# detectino.net
KiCad netlist of a schematic drawn in EAGLE
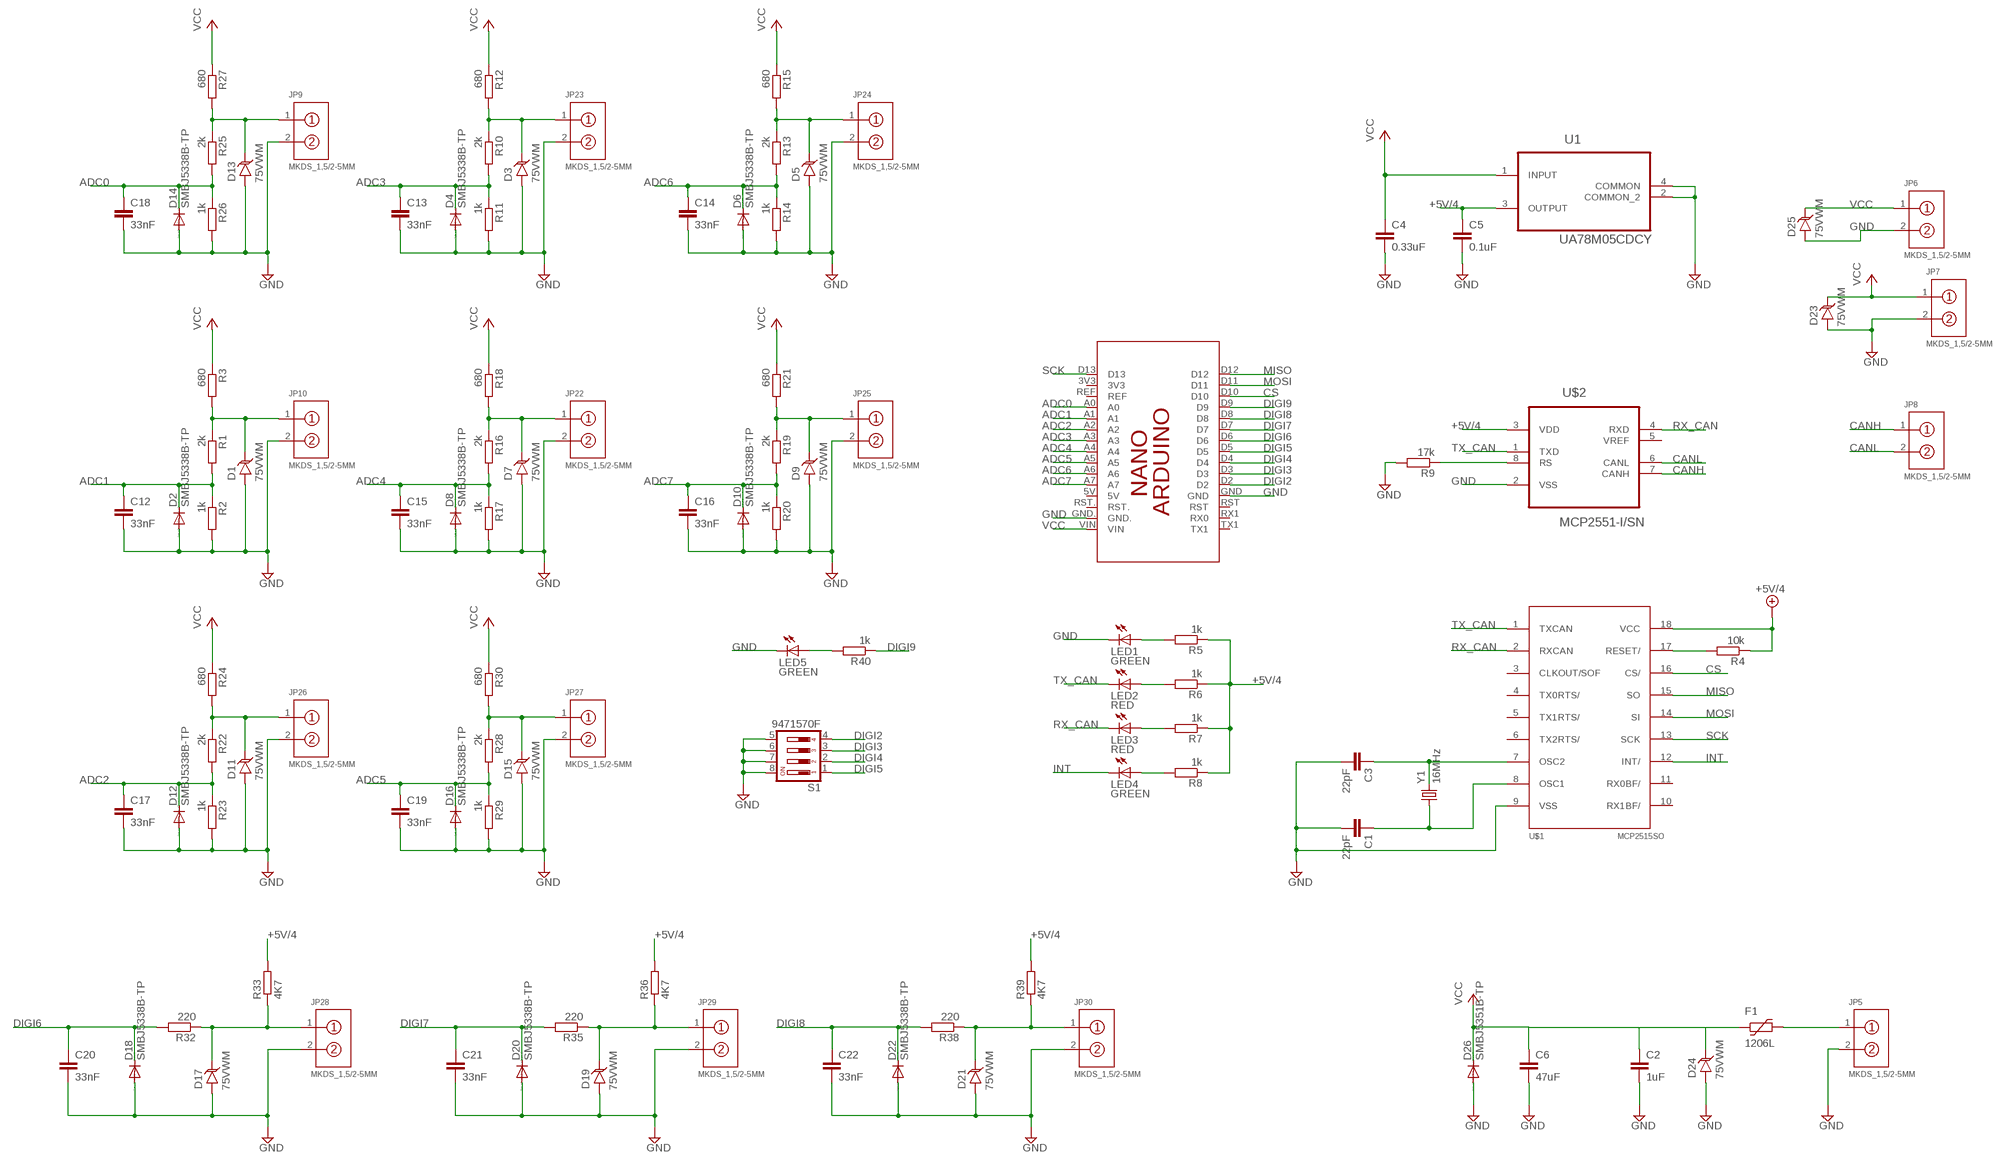
[diagram p0: schematic, sheet 1]

(export (version "E")
  (design (tool "Eeschema 10.0.6"))
  (components
    (comp (ref "C1")
      (value "22pF")
      (footprint "eagle-import:C1206K")
      (libsource (lib "eagle-import") (part "C-EUC1206K"))
    )
    (comp (ref "C2")
      (value "1uF")
      (footprint "eagle-import:C1206K")
      (libsource (lib "eagle-import") (part "C-EUC1206K"))
    )
    (comp (ref "C3")
      (value "22pF")
      (footprint "eagle-import:C1206K")
      (libsource (lib "eagle-import") (part "C-EUC1206K"))
    )
    (comp (ref "C4")
      (value "0.33uF")
      (footprint "eagle-import:C1206K")
      (libsource (lib "eagle-import") (part "C-EUC1206K"))
    )
    (comp (ref "C5")
      (value "0.1uF")
      (footprint "eagle-import:C1206K")
      (libsource (lib "eagle-import") (part "C-EUC1206K"))
    )
    (comp (ref "C6")
      (value "47uF")
      (footprint "eagle-import:C1206K")
      (libsource (lib "eagle-import") (part "C-EUC1206K"))
    )
    (comp (ref "C12")
      (value "33nF")
      (footprint "eagle-import:C1206K")
      (libsource (lib "eagle-import") (part "C-EUC1206K"))
    )
    (comp (ref "C13")
      (value "33nF")
      (footprint "eagle-import:C1206K")
      (libsource (lib "eagle-import") (part "C-EUC1206K"))
    )
    (comp (ref "C14")
      (value "33nF")
      (footprint "eagle-import:C1206K")
      (libsource (lib "eagle-import") (part "C-EUC1206K"))
    )
    (comp (ref "C15")
      (value "33nF")
      (footprint "eagle-import:C1206K")
      (libsource (lib "eagle-import") (part "C-EUC1206K"))
    )
    (comp (ref "C16")
      (value "33nF")
      (footprint "eagle-import:C1206K")
      (libsource (lib "eagle-import") (part "C-EUC1206K"))
    )
    (comp (ref "C17")
      (value "33nF")
      (footprint "eagle-import:C1206K")
      (libsource (lib "eagle-import") (part "C-EUC1206K"))
    )
    (comp (ref "C18")
      (value "33nF")
      (footprint "eagle-import:C1206K")
      (libsource (lib "eagle-import") (part "C-EUC1206K"))
    )
    (comp (ref "C19")
      (value "33nF")
      (footprint "eagle-import:C1206K")
      (libsource (lib "eagle-import") (part "C-EUC1206K"))
    )
    (comp (ref "C20")
      (value "33nF")
      (footprint "eagle-import:C1206K")
      (libsource (lib "eagle-import") (part "C-EUC1206K"))
    )
    (comp (ref "C21")
      (value "33nF")
      (footprint "eagle-import:C1206K")
      (libsource (lib "eagle-import") (part "C-EUC1206K"))
    )
    (comp (ref "C22")
      (value "33nF")
      (footprint "eagle-import:C1206K")
      (libsource (lib "eagle-import") (part "C-EUC1206K"))
    )
    (comp (ref "D1")
      (value "75VWM")
      (footprint "eagle-import:SMC")
      (libsource (lib "eagle-import") (part "TVS75VWM"))
    )
    (comp (ref "D2")
      (value "SMBJ5338B-TP")
      (footprint "eagle-import:DO214AA")
      (libsource (lib "eagle-import") (part "DIODE-DO214AA"))
    )
    (comp (ref "D3")
      (value "75VWM")
      (footprint "eagle-import:SMC")
      (libsource (lib "eagle-import") (part "TVS75VWM"))
    )
    (comp (ref "D4")
      (value "SMBJ5338B-TP")
      (footprint "eagle-import:DO214AA")
      (libsource (lib "eagle-import") (part "DIODE-DO214AA"))
    )
    (comp (ref "D5")
      (value "75VWM")
      (footprint "eagle-import:SMC")
      (libsource (lib "eagle-import") (part "TVS75VWM"))
    )
    (comp (ref "D6")
      (value "SMBJ5338B-TP")
      (footprint "eagle-import:DO214AA")
      (libsource (lib "eagle-import") (part "DIODE-DO214AA"))
    )
    (comp (ref "D7")
      (value "75VWM")
      (footprint "eagle-import:SMC")
      (libsource (lib "eagle-import") (part "TVS75VWM"))
    )
    (comp (ref "D8")
      (value "SMBJ5338B-TP")
      (footprint "eagle-import:DO214AA")
      (libsource (lib "eagle-import") (part "DIODE-DO214AA"))
    )
    (comp (ref "D9")
      (value "75VWM")
      (footprint "eagle-import:SMC")
      (libsource (lib "eagle-import") (part "TVS75VWM"))
    )
    (comp (ref "D10")
      (value "SMBJ5338B-TP")
      (footprint "eagle-import:DO214AA")
      (libsource (lib "eagle-import") (part "DIODE-DO214AA"))
    )
    (comp (ref "D11")
      (value "75VWM")
      (footprint "eagle-import:SMC")
      (libsource (lib "eagle-import") (part "TVS75VWM"))
    )
    (comp (ref "D12")
      (value "SMBJ5338B-TP")
      (footprint "eagle-import:DO214AA")
      (libsource (lib "eagle-import") (part "DIODE-DO214AA"))
    )
    (comp (ref "D13")
      (value "75VWM")
      (footprint "eagle-import:SMC")
      (libsource (lib "eagle-import") (part "TVS75VWM"))
    )
    (comp (ref "D14")
      (value "SMBJ5338B-TP")
      (footprint "eagle-import:DO214AA")
      (libsource (lib "eagle-import") (part "DIODE-DO214AA"))
    )
    (comp (ref "D15")
      (value "75VWM")
      (footprint "eagle-import:SMC")
      (libsource (lib "eagle-import") (part "TVS75VWM"))
    )
    (comp (ref "D16")
      (value "SMBJ5338B-TP")
      (footprint "eagle-import:DO214AA")
      (libsource (lib "eagle-import") (part "DIODE-DO214AA"))
    )
    (comp (ref "D17")
      (value "75VWM")
      (footprint "eagle-import:SMC")
      (libsource (lib "eagle-import") (part "TVS75VWM"))
    )
    (comp (ref "D18")
      (value "SMBJ5338B-TP")
      (footprint "eagle-import:DO214AA")
      (libsource (lib "eagle-import") (part "DIODE-DO214AA"))
    )
    (comp (ref "D19")
      (value "75VWM")
      (footprint "eagle-import:SMC")
      (libsource (lib "eagle-import") (part "TVS75VWM"))
    )
    (comp (ref "D20")
      (value "SMBJ5338B-TP")
      (footprint "eagle-import:DO214AA")
      (libsource (lib "eagle-import") (part "DIODE-DO214AA"))
    )
    (comp (ref "D21")
      (value "75VWM")
      (footprint "eagle-import:SMC")
      (libsource (lib "eagle-import") (part "TVS75VWM"))
    )
    (comp (ref "D22")
      (value "SMBJ5338B-TP")
      (footprint "eagle-import:DO214AA")
      (libsource (lib "eagle-import") (part "DIODE-DO214AA"))
    )
    (comp (ref "D23")
      (value "75VWM")
      (footprint "eagle-import:SMC")
      (libsource (lib "eagle-import") (part "TVS75VWM"))
    )
    (comp (ref "D24")
      (value "75VWM")
      (footprint "eagle-import:SMC")
      (libsource (lib "eagle-import") (part "TVS75VWM"))
    )
    (comp (ref "D25")
      (value "75VWM")
      (footprint "eagle-import:SMC")
      (libsource (lib "eagle-import") (part "TVS75VWM"))
    )
    (comp (ref "D26")
      (value "SMBJ5351B-TP")
      (footprint "eagle-import:DO214AA")
      (libsource (lib "eagle-import") (part "DIODE-DO214AA"))
    )
    (comp (ref "F1")
      (value "1206L")
      (footprint "eagle-import:1206L")
      (libsource (lib "eagle-import") (part "1206L"))
    )
    (comp (ref "JP5")
      (value "MKDS_1,5/2-5MM")
      (footprint "eagle-import:MKDS_1,5_2-5MM")
      (libsource (lib "eagle-import") (part "MKDS_1,5/2-5MM"))
    )
    (comp (ref "JP6")
      (value "MKDS_1,5/2-5MM")
      (footprint "eagle-import:MKDS_1,5_2-5MM")
      (libsource (lib "eagle-import") (part "MKDS_1,5/2-5MM"))
    )
    (comp (ref "JP7")
      (value "MKDS_1,5/2-5MM")
      (footprint "eagle-import:MKDS_1,5_2-5MM")
      (libsource (lib "eagle-import") (part "MKDS_1,5/2-5MM"))
    )
    (comp (ref "JP8")
      (value "MKDS_1,5/2-5MM")
      (footprint "eagle-import:MKDS_1,5_2-5MM")
      (libsource (lib "eagle-import") (part "MKDS_1,5/2-5MM"))
    )
    (comp (ref "JP9")
      (value "MKDS_1,5/2-5MM")
      (footprint "eagle-import:MKDS_1,5_2-5MM")
      (libsource (lib "eagle-import") (part "MKDS_1,5/2-5MM"))
    )
    (comp (ref "JP10")
      (value "MKDS_1,5/2-5MM")
      (footprint "eagle-import:MKDS_1,5_2-5MM")
      (libsource (lib "eagle-import") (part "MKDS_1,5/2-5MM"))
    )
    (comp (ref "JP22")
      (value "MKDS_1,5/2-5MM")
      (footprint "eagle-import:MKDS_1,5_2-5MM")
      (libsource (lib "eagle-import") (part "MKDS_1,5/2-5MM"))
    )
    (comp (ref "JP23")
      (value "MKDS_1,5/2-5MM")
      (footprint "eagle-import:MKDS_1,5_2-5MM")
      (libsource (lib "eagle-import") (part "MKDS_1,5/2-5MM"))
    )
    (comp (ref "JP24")
      (value "MKDS_1,5/2-5MM")
      (footprint "eagle-import:MKDS_1,5_2-5MM")
      (libsource (lib "eagle-import") (part "MKDS_1,5/2-5MM"))
    )
    (comp (ref "JP25")
      (value "MKDS_1,5/2-5MM")
      (footprint "eagle-import:MKDS_1,5_2-5MM")
      (libsource (lib "eagle-import") (part "MKDS_1,5/2-5MM"))
    )
    (comp (ref "JP26")
      (value "MKDS_1,5/2-5MM")
      (footprint "eagle-import:MKDS_1,5_2-5MM")
      (libsource (lib "eagle-import") (part "MKDS_1,5/2-5MM"))
    )
    (comp (ref "JP27")
      (value "MKDS_1,5/2-5MM")
      (footprint "eagle-import:MKDS_1,5_2-5MM")
      (libsource (lib "eagle-import") (part "MKDS_1,5/2-5MM"))
    )
    (comp (ref "JP28")
      (value "MKDS_1,5/2-5MM")
      (footprint "eagle-import:MKDS_1,5_2-5MM")
      (libsource (lib "eagle-import") (part "MKDS_1,5/2-5MM"))
    )
    (comp (ref "JP29")
      (value "MKDS_1,5/2-5MM")
      (footprint "eagle-import:MKDS_1,5_2-5MM")
      (libsource (lib "eagle-import") (part "MKDS_1,5/2-5MM"))
    )
    (comp (ref "JP30")
      (value "MKDS_1,5/2-5MM")
      (footprint "eagle-import:MKDS_1,5_2-5MM")
      (libsource (lib "eagle-import") (part "MKDS_1,5/2-5MM"))
    )
    (comp (ref "LED1")
      (value "GREEN")
      (footprint "eagle-import:SML1206")
      (libsource (lib "eagle-import") (part "LEDSML1206"))
    )
    (comp (ref "LED2")
      (value "RED")
      (footprint "eagle-import:SML1206")
      (libsource (lib "eagle-import") (part "LEDSML1206"))
    )
    (comp (ref "LED3")
      (value "RED")
      (footprint "eagle-import:SML1206")
      (libsource (lib "eagle-import") (part "LEDSML1206"))
    )
    (comp (ref "LED4")
      (value "GREEN")
      (footprint "eagle-import:SML1206")
      (libsource (lib "eagle-import") (part "LEDSML1206"))
    )
    (comp (ref "LED5")
      (value "GREEN")
      (footprint "eagle-import:SML1206")
      (libsource (lib "eagle-import") (part "LEDSML1206"))
    )
    (comp (ref "PCB2")
      (value "ARDUINO_NANO")
      (footprint "eagle-import:ARDUINO_NANO")
      (libsource (lib "eagle-import") (part "ARDUINO_NANO"))
    )
    (comp (ref "R1")
      (value "2k")
      (footprint "eagle-import:R1206")
      (libsource (lib "eagle-import") (part "R-EU_R1206"))
    )
    (comp (ref "R2")
      (value "1k")
      (footprint "eagle-import:R1206")
      (libsource (lib "eagle-import") (part "R-EU_R1206"))
    )
    (comp (ref "R3")
      (value "680")
      (footprint "eagle-import:R1206")
      (libsource (lib "eagle-import") (part "R-EU_R1206"))
    )
    (comp (ref "R4")
      (value "10k")
      (footprint "eagle-import:R1206")
      (libsource (lib "eagle-import") (part "R-EU_R1206"))
    )
    (comp (ref "R5")
      (value "1k")
      (footprint "eagle-import:R1206")
      (libsource (lib "eagle-import") (part "R-EU_R1206"))
    )
    (comp (ref "R6")
      (value "1k")
      (footprint "eagle-import:R1206")
      (libsource (lib "eagle-import") (part "R-EU_R1206"))
    )
    (comp (ref "R7")
      (value "1k")
      (footprint "eagle-import:R1206")
      (libsource (lib "eagle-import") (part "R-EU_R1206"))
    )
    (comp (ref "R8")
      (value "1k")
      (footprint "eagle-import:R1206")
      (libsource (lib "eagle-import") (part "R-EU_R1206"))
    )
    (comp (ref "R9")
      (value "17k")
      (footprint "eagle-import:R1206")
      (libsource (lib "eagle-import") (part "R-EU_R1206"))
    )
    (comp (ref "R10")
      (value "2k")
      (footprint "eagle-import:R1206")
      (libsource (lib "eagle-import") (part "R-EU_R1206"))
    )
    (comp (ref "R11")
      (value "1k")
      (footprint "eagle-import:R1206")
      (libsource (lib "eagle-import") (part "R-EU_R1206"))
    )
    (comp (ref "R12")
      (value "680")
      (footprint "eagle-import:R1206")
      (libsource (lib "eagle-import") (part "R-EU_R1206"))
    )
    (comp (ref "R13")
      (value "2k")
      (footprint "eagle-import:R1206")
      (libsource (lib "eagle-import") (part "R-EU_R1206"))
    )
    (comp (ref "R14")
      (value "1k")
      (footprint "eagle-import:R1206")
      (libsource (lib "eagle-import") (part "R-EU_R1206"))
    )
    (comp (ref "R15")
      (value "680")
      (footprint "eagle-import:R1206")
      (libsource (lib "eagle-import") (part "R-EU_R1206"))
    )
    (comp (ref "R16")
      (value "2k")
      (footprint "eagle-import:R1206")
      (libsource (lib "eagle-import") (part "R-EU_R1206"))
    )
    (comp (ref "R17")
      (value "1k")
      (footprint "eagle-import:R1206")
      (libsource (lib "eagle-import") (part "R-EU_R1206"))
    )
    (comp (ref "R18")
      (value "680")
      (footprint "eagle-import:R1206")
      (libsource (lib "eagle-import") (part "R-EU_R1206"))
    )
    (comp (ref "R19")
      (value "2k")
      (footprint "eagle-import:R1206")
      (libsource (lib "eagle-import") (part "R-EU_R1206"))
    )
    (comp (ref "R20")
      (value "1k")
      (footprint "eagle-import:R1206")
      (libsource (lib "eagle-import") (part "R-EU_R1206"))
    )
    (comp (ref "R21")
      (value "680")
      (footprint "eagle-import:R1206")
      (libsource (lib "eagle-import") (part "R-EU_R1206"))
    )
    (comp (ref "R22")
      (value "2k")
      (footprint "eagle-import:R1206")
      (libsource (lib "eagle-import") (part "R-EU_R1206"))
    )
    (comp (ref "R23")
      (value "1k")
      (footprint "eagle-import:R1206")
      (libsource (lib "eagle-import") (part "R-EU_R1206"))
    )
    (comp (ref "R24")
      (value "680")
      (footprint "eagle-import:R1206")
      (libsource (lib "eagle-import") (part "R-EU_R1206"))
    )
    (comp (ref "R25")
      (value "2k")
      (footprint "eagle-import:R1206")
      (libsource (lib "eagle-import") (part "R-EU_R1206"))
    )
    (comp (ref "R26")
      (value "1k")
      (footprint "eagle-import:R1206")
      (libsource (lib "eagle-import") (part "R-EU_R1206"))
    )
    (comp (ref "R27")
      (value "680")
      (footprint "eagle-import:R1206")
      (libsource (lib "eagle-import") (part "R-EU_R1206"))
    )
    (comp (ref "R28")
      (value "2k")
      (footprint "eagle-import:R1206")
      (libsource (lib "eagle-import") (part "R-EU_R1206"))
    )
    (comp (ref "R29")
      (value "1k")
      (footprint "eagle-import:R1206")
      (libsource (lib "eagle-import") (part "R-EU_R1206"))
    )
    (comp (ref "R30")
      (value "680")
      (footprint "eagle-import:R1206")
      (libsource (lib "eagle-import") (part "R-EU_R1206"))
    )
    (comp (ref "R32")
      (value "220")
      (footprint "eagle-import:R1206")
      (libsource (lib "eagle-import") (part "R-EU_R1206"))
    )
    (comp (ref "R33")
      (value "4K7")
      (footprint "eagle-import:R1206")
      (libsource (lib "eagle-import") (part "R-EU_R1206"))
    )
    (comp (ref "R35")
      (value "220")
      (footprint "eagle-import:R1206")
      (libsource (lib "eagle-import") (part "R-EU_R1206"))
    )
    (comp (ref "R36")
      (value "4K7")
      (footprint "eagle-import:R1206")
      (libsource (lib "eagle-import") (part "R-EU_R1206"))
    )
    (comp (ref "R38")
      (value "220")
      (footprint "eagle-import:R1206")
      (libsource (lib "eagle-import") (part "R-EU_R1206"))
    )
    (comp (ref "R39")
      (value "4K7")
      (footprint "eagle-import:R1206")
      (libsource (lib "eagle-import") (part "R-EU_R1206"))
    )
    (comp (ref "R40")
      (value "1k")
      (footprint "eagle-import:R1206")
      (libsource (lib "eagle-import") (part "R-EU_R1206"))
    )
    (comp (ref "S1")
      (value "9471570F")
      (footprint "eagle-import:DS-04")
      (libsource (lib "eagle-import") (part "DS04"))
    )
    (comp (ref "U$1")
      (value "MCP2515SO")
      (footprint "eagle-import:SO18L")
      (libsource (lib "eagle-import") (part "MCP2515SO"))
    )
    (comp (ref "U$2")
      (value "MCP2551-I/SN")
      (footprint "eagle-import:SOIC127P600X175-8N")
      (libsource (lib "eagle-import") (part "MCP2551-I/SN"))
    )
    (comp (ref "U1")
      (value "UA78M05CDCY")
      (footprint "eagle-import:SOT230P700X180-4N")
      (libsource (lib "eagle-import") (part "UA78M05CDCY"))
    )
    (comp (ref "Y1")
      (value "16MHz")
      (footprint "eagle-import:HC49US")
      (libsource (lib "eagle-import") (part "CRYSTALHC49US"))
    )
  )
  (nets
    (net (code "1") (name "+5V{slash}4") (class "Default")
      (node (ref "C5") (pin "1") (pinfunction "1_1") (pintype "passive"))
      (node (ref "R33") (pin "2") (pinfunction "2_2") (pintype "passive"))
      (node (ref "R36") (pin "2") (pinfunction "2_2") (pintype "passive"))
      (node (ref "R39") (pin "2") (pinfunction "2_2") (pintype "passive"))
      (node (ref "R4") (pin "1") (pinfunction "1_1") (pintype "passive"))
      (node (ref "R5") (pin "1") (pinfunction "1_1") (pintype "passive"))
      (node (ref "R6") (pin "1") (pinfunction "1_1") (pintype "passive"))
      (node (ref "R7") (pin "1") (pinfunction "1_1") (pintype "passive"))
      (node (ref "R8") (pin "1") (pinfunction "1_1") (pintype "passive"))
      (node (ref "U$1") (pin "18") (pinfunction "VCC_18") (pintype "power_in"))
      (node (ref "U$2") (pin "3") (pinfunction "VDD_3") (pintype "power_in"))
      (node (ref "U1") (pin "3") (pinfunction "OUTPUT_3") (pintype "input"))
    )
    (net (code "2") (name "/ADC0") (class "Default")
      (node (ref "C18") (pin "1") (pinfunction "1_1") (pintype "passive"))
      (node (ref "D14") (pin "C") (pinfunction "C_C") (pintype "passive"))
      (node (ref "PCB2") (pin "A0") (pinfunction "A0_A0") (pintype "bidirectional"))
      (node (ref "R25") (pin "2") (pinfunction "2_2") (pintype "passive"))
      (node (ref "R26") (pin "1") (pinfunction "1_1") (pintype "passive"))
    )
    (net (code "3") (name "/ADC1") (class "Default")
      (node (ref "C12") (pin "1") (pinfunction "1_1") (pintype "passive"))
      (node (ref "D2") (pin "C") (pinfunction "C_C") (pintype "passive"))
      (node (ref "PCB2") (pin "A1") (pinfunction "A1_A1") (pintype "bidirectional"))
      (node (ref "R1") (pin "2") (pinfunction "2_2") (pintype "passive"))
      (node (ref "R2") (pin "1") (pinfunction "1_1") (pintype "passive"))
    )
    (net (code "4") (name "/ADC2") (class "Default")
      (node (ref "C17") (pin "1") (pinfunction "1_1") (pintype "passive"))
      (node (ref "D12") (pin "C") (pinfunction "C_C") (pintype "passive"))
      (node (ref "PCB2") (pin "A2") (pinfunction "A2_A2") (pintype "bidirectional"))
      (node (ref "R22") (pin "2") (pinfunction "2_2") (pintype "passive"))
      (node (ref "R23") (pin "1") (pinfunction "1_1") (pintype "passive"))
    )
    (net (code "5") (name "/ADC3") (class "Default")
      (node (ref "C13") (pin "1") (pinfunction "1_1") (pintype "passive"))
      (node (ref "D4") (pin "C") (pinfunction "C_C") (pintype "passive"))
      (node (ref "PCB2") (pin "A3") (pinfunction "A3_A3") (pintype "bidirectional"))
      (node (ref "R10") (pin "2") (pinfunction "2_2") (pintype "passive"))
      (node (ref "R11") (pin "1") (pinfunction "1_1") (pintype "passive"))
    )
    (net (code "6") (name "/ADC4") (class "Default")
      (node (ref "C15") (pin "1") (pinfunction "1_1") (pintype "passive"))
      (node (ref "D8") (pin "C") (pinfunction "C_C") (pintype "passive"))
      (node (ref "PCB2") (pin "A4") (pinfunction "A4_A4") (pintype "bidirectional"))
      (node (ref "R16") (pin "2") (pinfunction "2_2") (pintype "passive"))
      (node (ref "R17") (pin "1") (pinfunction "1_1") (pintype "passive"))
    )
    (net (code "7") (name "/ADC5") (class "Default")
      (node (ref "C19") (pin "1") (pinfunction "1_1") (pintype "passive"))
      (node (ref "D16") (pin "C") (pinfunction "C_C") (pintype "passive"))
      (node (ref "PCB2") (pin "A5") (pinfunction "A5_A5") (pintype "bidirectional"))
      (node (ref "R28") (pin "2") (pinfunction "2_2") (pintype "passive"))
      (node (ref "R29") (pin "1") (pinfunction "1_1") (pintype "passive"))
    )
    (net (code "8") (name "/ADC6") (class "Default")
      (node (ref "C14") (pin "1") (pinfunction "1_1") (pintype "passive"))
      (node (ref "D6") (pin "C") (pinfunction "C_C") (pintype "passive"))
      (node (ref "PCB2") (pin "A6") (pinfunction "A6_A6") (pintype "bidirectional"))
      (node (ref "R13") (pin "2") (pinfunction "2_2") (pintype "passive"))
      (node (ref "R14") (pin "1") (pinfunction "1_1") (pintype "passive"))
    )
    (net (code "9") (name "/ADC7") (class "Default")
      (node (ref "C16") (pin "1") (pinfunction "1_1") (pintype "passive"))
      (node (ref "D10") (pin "C") (pinfunction "C_C") (pintype "passive"))
      (node (ref "PCB2") (pin "A7") (pinfunction "A7_A7") (pintype "bidirectional"))
      (node (ref "R19") (pin "2") (pinfunction "2_2") (pintype "passive"))
      (node (ref "R20") (pin "1") (pinfunction "1_1") (pintype "passive"))
    )
    (net (code "10") (name "/CANH") (class "Default")
      (node (ref "JP8") (pin "1") (pinfunction "P$1_1") (pintype "bidirectional"))
      (node (ref "U$2") (pin "7") (pinfunction "CANH_7") (pintype "bidirectional"))
    )
    (net (code "11") (name "/CANL") (class "Default")
      (node (ref "JP8") (pin "2") (pinfunction "P$2_2") (pintype "bidirectional"))
      (node (ref "U$2") (pin "6") (pinfunction "CANL_6") (pintype "bidirectional"))
    )
    (net (code "12") (name "/CS") (class "Default")
      (node (ref "PCB2") (pin "D10") (pinfunction "D10_D10") (pintype "bidirectional"))
      (node (ref "U$1") (pin "16") (pinfunction "CS/_16") (pintype "input"))
    )
    (net (code "13") (name "/DIGI2") (class "Default")
      (node (ref "PCB2") (pin "D2") (pinfunction "D2_D2") (pintype "bidirectional"))
      (node (ref "S1") (pin "4") (pinfunction "4_4") (pintype "passive"))
    )
    (net (code "14") (name "/DIGI3") (class "Default")
      (node (ref "PCB2") (pin "D3") (pinfunction "D3_D3") (pintype "bidirectional"))
      (node (ref "S1") (pin "3") (pinfunction "3_3") (pintype "passive"))
    )
    (net (code "15") (name "/DIGI4") (class "Default")
      (node (ref "PCB2") (pin "D4") (pinfunction "D4_D4") (pintype "bidirectional"))
      (node (ref "S1") (pin "2") (pinfunction "2_2") (pintype "passive"))
    )
    (net (code "16") (name "/DIGI5") (class "Default")
      (node (ref "PCB2") (pin "D5") (pinfunction "D5_D5") (pintype "bidirectional"))
      (node (ref "S1") (pin "1") (pinfunction "1_1") (pintype "passive"))
    )
    (net (code "17") (name "/DIGI6") (class "Default")
      (node (ref "C20") (pin "1") (pinfunction "1_1") (pintype "passive"))
      (node (ref "D18") (pin "C") (pinfunction "C_C") (pintype "passive"))
      (node (ref "PCB2") (pin "D6") (pinfunction "D6_D6") (pintype "bidirectional"))
      (node (ref "R32") (pin "2") (pinfunction "2_2") (pintype "passive"))
    )
    (net (code "18") (name "/DIGI7") (class "Default")
      (node (ref "C21") (pin "1") (pinfunction "1_1") (pintype "passive"))
      (node (ref "D20") (pin "C") (pinfunction "C_C") (pintype "passive"))
      (node (ref "PCB2") (pin "D7") (pinfunction "D7_D7") (pintype "bidirectional"))
      (node (ref "R35") (pin "2") (pinfunction "2_2") (pintype "passive"))
    )
    (net (code "19") (name "/DIGI8") (class "Default")
      (node (ref "C22") (pin "1") (pinfunction "1_1") (pintype "passive"))
      (node (ref "D22") (pin "C") (pinfunction "C_C") (pintype "passive"))
      (node (ref "PCB2") (pin "D8") (pinfunction "D8_D8") (pintype "bidirectional"))
      (node (ref "R38") (pin "2") (pinfunction "2_2") (pintype "passive"))
    )
    (net (code "20") (name "/DIGI9") (class "Default")
      (node (ref "PCB2") (pin "D9") (pinfunction "D9_D9") (pintype "bidirectional"))
      (node (ref "R40") (pin "1") (pinfunction "1_1") (pintype "passive"))
    )
    (net (code "21") (name "/INT") (class "Default")
      (node (ref "LED4") (pin "C") (pinfunction "C_C") (pintype "passive"))
      (node (ref "U$1") (pin "12") (pinfunction "INT/_12") (pintype "output"))
    )
    (net (code "22") (name "/MISO") (class "Default")
      (node (ref "PCB2") (pin "D12") (pinfunction "D12_D12") (pintype "bidirectional"))
      (node (ref "U$1") (pin "15") (pinfunction "SO_15") (pintype "output"))
    )
    (net (code "23") (name "/MOSI") (class "Default")
      (node (ref "PCB2") (pin "D11") (pinfunction "D11_D11") (pintype "bidirectional"))
      (node (ref "U$1") (pin "14") (pinfunction "SI_14") (pintype "input"))
    )
    (net (code "24") (name "/RX_CAN") (class "Default")
      (node (ref "LED3") (pin "C") (pinfunction "C_C") (pintype "passive"))
      (node (ref "U$1") (pin "2") (pinfunction "RXCAN_2") (pintype "input"))
      (node (ref "U$2") (pin "4") (pinfunction "RXD_4") (pintype "output"))
    )
    (net (code "25") (name "/SCK") (class "Default")
      (node (ref "PCB2") (pin "D13") (pinfunction "D13_D13") (pintype "bidirectional"))
      (node (ref "U$1") (pin "13") (pinfunction "SCK_13") (pintype "input"))
    )
    (net (code "26") (name "/TX_CAN") (class "Default")
      (node (ref "LED2") (pin "C") (pinfunction "C_C") (pintype "passive"))
      (node (ref "U$1") (pin "1") (pinfunction "TXCAN_1") (pintype "output"))
      (node (ref "U$2") (pin "1") (pinfunction "TXD_1") (pintype "input"))
    )
    (net (code "27") (name "GND") (class "Default")
      (node (ref "C1") (pin "2") (pinfunction "2_2") (pintype "passive"))
      (node (ref "C12") (pin "2") (pinfunction "2_2") (pintype "passive"))
      (node (ref "C13") (pin "2") (pinfunction "2_2") (pintype "passive"))
      (node (ref "C14") (pin "2") (pinfunction "2_2") (pintype "passive"))
      (node (ref "C15") (pin "2") (pinfunction "2_2") (pintype "passive"))
      (node (ref "C16") (pin "2") (pinfunction "2_2") (pintype "passive"))
      (node (ref "C17") (pin "2") (pinfunction "2_2") (pintype "passive"))
      (node (ref "C18") (pin "2") (pinfunction "2_2") (pintype "passive"))
      (node (ref "C19") (pin "2") (pinfunction "2_2") (pintype "passive"))
      (node (ref "C2") (pin "2") (pinfunction "2_2") (pintype "passive"))
      (node (ref "C20") (pin "2") (pinfunction "2_2") (pintype "passive"))
      (node (ref "C21") (pin "2") (pinfunction "2_2") (pintype "passive"))
      (node (ref "C22") (pin "2") (pinfunction "2_2") (pintype "passive"))
      (node (ref "C3") (pin "2") (pinfunction "2_2") (pintype "passive"))
      (node (ref "C4") (pin "2") (pinfunction "2_2") (pintype "passive"))
      (node (ref "C5") (pin "2") (pinfunction "2_2") (pintype "passive"))
      (node (ref "C6") (pin "2") (pinfunction "2_2") (pintype "passive"))
      (node (ref "D1") (pin "A") (pinfunction "A_A") (pintype "passive"))
      (node (ref "D10") (pin "A") (pinfunction "A_A") (pintype "passive"))
      (node (ref "D11") (pin "A") (pinfunction "A_A") (pintype "passive"))
      (node (ref "D12") (pin "A") (pinfunction "A_A") (pintype "passive"))
      (node (ref "D13") (pin "A") (pinfunction "A_A") (pintype "passive"))
      (node (ref "D14") (pin "A") (pinfunction "A_A") (pintype "passive"))
      (node (ref "D15") (pin "A") (pinfunction "A_A") (pintype "passive"))
      (node (ref "D16") (pin "A") (pinfunction "A_A") (pintype "passive"))
      (node (ref "D17") (pin "A") (pinfunction "A_A") (pintype "passive"))
      (node (ref "D18") (pin "A") (pinfunction "A_A") (pintype "passive"))
      (node (ref "D19") (pin "A") (pinfunction "A_A") (pintype "passive"))
      (node (ref "D2") (pin "A") (pinfunction "A_A") (pintype "passive"))
      (node (ref "D20") (pin "A") (pinfunction "A_A") (pintype "passive"))
      (node (ref "D21") (pin "A") (pinfunction "A_A") (pintype "passive"))
      (node (ref "D22") (pin "A") (pinfunction "A_A") (pintype "passive"))
      (node (ref "D23") (pin "A") (pinfunction "A_A") (pintype "passive"))
      (node (ref "D24") (pin "A") (pinfunction "A_A") (pintype "passive"))
      (node (ref "D25") (pin "A") (pinfunction "A_A") (pintype "passive"))
      (node (ref "D26") (pin "A") (pinfunction "A_A") (pintype "passive"))
      (node (ref "D3") (pin "A") (pinfunction "A_A") (pintype "passive"))
      (node (ref "D4") (pin "A") (pinfunction "A_A") (pintype "passive"))
      (node (ref "D5") (pin "A") (pinfunction "A_A") (pintype "passive"))
      (node (ref "D6") (pin "A") (pinfunction "A_A") (pintype "passive"))
      (node (ref "D7") (pin "A") (pinfunction "A_A") (pintype "passive"))
      (node (ref "D8") (pin "A") (pinfunction "A_A") (pintype "passive"))
      (node (ref "D9") (pin "A") (pinfunction "A_A") (pintype "passive"))
      (node (ref "JP10") (pin "2") (pinfunction "P$2_2") (pintype "bidirectional"))
      (node (ref "JP22") (pin "2") (pinfunction "P$2_2") (pintype "bidirectional"))
      (node (ref "JP23") (pin "2") (pinfunction "P$2_2") (pintype "bidirectional"))
      (node (ref "JP24") (pin "2") (pinfunction "P$2_2") (pintype "bidirectional"))
      (node (ref "JP25") (pin "2") (pinfunction "P$2_2") (pintype "bidirectional"))
      (node (ref "JP26") (pin "2") (pinfunction "P$2_2") (pintype "bidirectional"))
      (node (ref "JP27") (pin "2") (pinfunction "P$2_2") (pintype "bidirectional"))
      (node (ref "JP28") (pin "2") (pinfunction "P$2_2") (pintype "bidirectional"))
      (node (ref "JP29") (pin "2") (pinfunction "P$2_2") (pintype "bidirectional"))
      (node (ref "JP30") (pin "2") (pinfunction "P$2_2") (pintype "bidirectional"))
      (node (ref "JP5") (pin "2") (pinfunction "P$2_2") (pintype "bidirectional"))
      (node (ref "JP6") (pin "2") (pinfunction "P$2_2") (pintype "bidirectional"))
      (node (ref "JP7") (pin "2") (pinfunction "P$2_2") (pintype "bidirectional"))
      (node (ref "JP9") (pin "2") (pinfunction "P$2_2") (pintype "bidirectional"))
      (node (ref "LED1") (pin "C") (pinfunction "C_C") (pintype "passive"))
      (node (ref "LED5") (pin "C") (pinfunction "C_C") (pintype "passive"))
      (node (ref "PCB2") (pin "GND") (pinfunction "GND_GND") (pintype "bidirectional"))
      (node (ref "PCB2") (pin "GND.") (pinfunction "GND._GND.") (pintype "bidirectional"))
      (node (ref "R11") (pin "2") (pinfunction "2_2") (pintype "passive"))
      (node (ref "R14") (pin "2") (pinfunction "2_2") (pintype "passive"))
      (node (ref "R17") (pin "2") (pinfunction "2_2") (pintype "passive"))
      (node (ref "R2") (pin "2") (pinfunction "2_2") (pintype "passive"))
      (node (ref "R20") (pin "2") (pinfunction "2_2") (pintype "passive"))
      (node (ref "R23") (pin "2") (pinfunction "2_2") (pintype "passive"))
      (node (ref "R26") (pin "2") (pinfunction "2_2") (pintype "passive"))
      (node (ref "R29") (pin "2") (pinfunction "2_2") (pintype "passive"))
      (node (ref "R9") (pin "2") (pinfunction "2_2") (pintype "passive"))
      (node (ref "S1") (pin "5") (pinfunction "5_5") (pintype "passive"))
      (node (ref "S1") (pin "6") (pinfunction "6_6") (pintype "passive"))
      (node (ref "S1") (pin "7") (pinfunction "7_7") (pintype "passive"))
      (node (ref "S1") (pin "8") (pinfunction "8_8") (pintype "passive"))
      (node (ref "U$1") (pin "9") (pinfunction "VSS_9") (pintype "power_in"))
      (node (ref "U$2") (pin "2") (pinfunction "VSS_2") (pintype "passive"))
      (node (ref "U1") (pin "2") (pinfunction "COMMON_2_2") (pintype "output"))
      (node (ref "U1") (pin "4") (pinfunction "COMMON_4") (pintype "output"))
    )
    (net (code "28") (name "Net-(F1-2)") (class "Default")
      (node (ref "F1") (pin "P$2") (pinfunction "2_P$2") (pintype "passive"))
      (node (ref "JP5") (pin "1") (pinfunction "P$1_1") (pintype "bidirectional"))
    )
    (net (code "29") (name "Net-(JP9-P$1)") (class "Default")
      (node (ref "D13") (pin "C") (pinfunction "C_C") (pintype "passive"))
      (node (ref "JP9") (pin "1") (pinfunction "P$1_1") (pintype "bidirectional"))
      (node (ref "R25") (pin "1") (pinfunction "1_1") (pintype "passive"))
      (node (ref "R27") (pin "2") (pinfunction "2_2") (pintype "passive"))
    )
    (net (code "30") (name "Net-(JP10-P$1)") (class "Default")
      (node (ref "D1") (pin "C") (pinfunction "C_C") (pintype "passive"))
      (node (ref "JP10") (pin "1") (pinfunction "P$1_1") (pintype "bidirectional"))
      (node (ref "R1") (pin "1") (pinfunction "1_1") (pintype "passive"))
      (node (ref "R3") (pin "2") (pinfunction "2_2") (pintype "passive"))
    )
    (net (code "31") (name "Net-(JP22-P$1)") (class "Default")
      (node (ref "D7") (pin "C") (pinfunction "C_C") (pintype "passive"))
      (node (ref "JP22") (pin "1") (pinfunction "P$1_1") (pintype "bidirectional"))
      (node (ref "R16") (pin "1") (pinfunction "1_1") (pintype "passive"))
      (node (ref "R18") (pin "2") (pinfunction "2_2") (pintype "passive"))
    )
    (net (code "32") (name "Net-(JP23-P$1)") (class "Default")
      (node (ref "D3") (pin "C") (pinfunction "C_C") (pintype "passive"))
      (node (ref "JP23") (pin "1") (pinfunction "P$1_1") (pintype "bidirectional"))
      (node (ref "R10") (pin "1") (pinfunction "1_1") (pintype "passive"))
      (node (ref "R12") (pin "2") (pinfunction "2_2") (pintype "passive"))
    )
    (net (code "33") (name "Net-(JP24-P$1)") (class "Default")
      (node (ref "D5") (pin "C") (pinfunction "C_C") (pintype "passive"))
      (node (ref "JP24") (pin "1") (pinfunction "P$1_1") (pintype "bidirectional"))
      (node (ref "R13") (pin "1") (pinfunction "1_1") (pintype "passive"))
      (node (ref "R15") (pin "2") (pinfunction "2_2") (pintype "passive"))
    )
    (net (code "34") (name "Net-(JP25-P$1)") (class "Default")
      (node (ref "D9") (pin "C") (pinfunction "C_C") (pintype "passive"))
      (node (ref "JP25") (pin "1") (pinfunction "P$1_1") (pintype "bidirectional"))
      (node (ref "R19") (pin "1") (pinfunction "1_1") (pintype "passive"))
      (node (ref "R21") (pin "2") (pinfunction "2_2") (pintype "passive"))
    )
    (net (code "35") (name "Net-(JP26-P$1)") (class "Default")
      (node (ref "D11") (pin "C") (pinfunction "C_C") (pintype "passive"))
      (node (ref "JP26") (pin "1") (pinfunction "P$1_1") (pintype "bidirectional"))
      (node (ref "R22") (pin "1") (pinfunction "1_1") (pintype "passive"))
      (node (ref "R24") (pin "2") (pinfunction "2_2") (pintype "passive"))
    )
    (net (code "36") (name "Net-(JP27-P$1)") (class "Default")
      (node (ref "D15") (pin "C") (pinfunction "C_C") (pintype "passive"))
      (node (ref "JP27") (pin "1") (pinfunction "P$1_1") (pintype "bidirectional"))
      (node (ref "R28") (pin "1") (pinfunction "1_1") (pintype "passive"))
      (node (ref "R30") (pin "2") (pinfunction "2_2") (pintype "passive"))
    )
    (net (code "37") (name "Net-(JP28-P$1)") (class "Default")
      (node (ref "D17") (pin "C") (pinfunction "C_C") (pintype "passive"))
      (node (ref "JP28") (pin "1") (pinfunction "P$1_1") (pintype "bidirectional"))
      (node (ref "R32") (pin "1") (pinfunction "1_1") (pintype "passive"))
      (node (ref "R33") (pin "1") (pinfunction "1_1") (pintype "passive"))
    )
    (net (code "38") (name "Net-(JP29-P$1)") (class "Default")
      (node (ref "D19") (pin "C") (pinfunction "C_C") (pintype "passive"))
      (node (ref "JP29") (pin "1") (pinfunction "P$1_1") (pintype "bidirectional"))
      (node (ref "R35") (pin "1") (pinfunction "1_1") (pintype "passive"))
      (node (ref "R36") (pin "1") (pinfunction "1_1") (pintype "passive"))
    )
    (net (code "39") (name "Net-(JP30-P$1)") (class "Default")
      (node (ref "D21") (pin "C") (pinfunction "C_C") (pintype "passive"))
      (node (ref "JP30") (pin "1") (pinfunction "P$1_1") (pintype "bidirectional"))
      (node (ref "R38") (pin "1") (pinfunction "1_1") (pintype "passive"))
      (node (ref "R39") (pin "1") (pinfunction "1_1") (pintype "passive"))
    )
    (net (code "40") (name "Net-(LED1-PadA)") (class "Default")
      (node (ref "LED1") (pin "A") (pinfunction "A_A") (pintype "passive"))
      (node (ref "R5") (pin "2") (pinfunction "2_2") (pintype "passive"))
    )
    (net (code "41") (name "Net-(LED2-PadA)") (class "Default")
      (node (ref "LED2") (pin "A") (pinfunction "A_A") (pintype "passive"))
      (node (ref "R6") (pin "2") (pinfunction "2_2") (pintype "passive"))
    )
    (net (code "42") (name "Net-(LED3-PadA)") (class "Default")
      (node (ref "LED3") (pin "A") (pinfunction "A_A") (pintype "passive"))
      (node (ref "R7") (pin "2") (pinfunction "2_2") (pintype "passive"))
    )
    (net (code "43") (name "Net-(LED4-PadA)") (class "Default")
      (node (ref "LED4") (pin "A") (pinfunction "A_A") (pintype "passive"))
      (node (ref "R8") (pin "2") (pinfunction "2_2") (pintype "passive"))
    )
    (net (code "44") (name "Net-(LED5-PadA)") (class "Default")
      (node (ref "LED5") (pin "A") (pinfunction "A_A") (pintype "passive"))
      (node (ref "R40") (pin "2") (pinfunction "2_2") (pintype "passive"))
    )
    (net (code "45") (name "Net-(U$1-OSC1)") (class "Default")
      (node (ref "C1") (pin "1") (pinfunction "1_1") (pintype "passive"))
      (node (ref "U$1") (pin "8") (pinfunction "OSC1_8") (pintype "bidirectional"))
      (node (ref "Y1") (pin "1") (pinfunction "1_1") (pintype "passive"))
    )
    (net (code "46") (name "Net-(U$1-OSC2)") (class "Default")
      (node (ref "C3") (pin "1") (pinfunction "1_1") (pintype "passive"))
      (node (ref "U$1") (pin "7") (pinfunction "OSC2_7") (pintype "bidirectional"))
      (node (ref "Y1") (pin "2") (pinfunction "2_2") (pintype "passive"))
    )
    (net (code "47") (name "Net-(U$1-RESET{slash})") (class "Default")
      (node (ref "R4") (pin "2") (pinfunction "2_2") (pintype "passive"))
      (node (ref "U$1") (pin "17") (pinfunction "RESET/_17") (pintype "input"))
    )
    (net (code "48") (name "Net-(U$2-RS)") (class "Default")
      (node (ref "R9") (pin "1") (pinfunction "1_1") (pintype "passive"))
      (node (ref "U$2") (pin "8") (pinfunction "RS_8") (pintype "input"))
    )
    (net (code "49") (name "VCC") (class "Default")
      (node (ref "C2") (pin "1") (pinfunction "1_1") (pintype "passive"))
      (node (ref "C4") (pin "1") (pinfunction "1_1") (pintype "passive"))
      (node (ref "C6") (pin "1") (pinfunction "1_1") (pintype "passive"))
      (node (ref "D23") (pin "C") (pinfunction "C_C") (pintype "passive"))
      (node (ref "D24") (pin "C") (pinfunction "C_C") (pintype "passive"))
      (node (ref "D25") (pin "C") (pinfunction "C_C") (pintype "passive"))
      (node (ref "D26") (pin "C") (pinfunction "C_C") (pintype "passive"))
      (node (ref "F1") (pin "P$1") (pinfunction "1_P$1") (pintype "passive"))
      (node (ref "JP6") (pin "1") (pinfunction "P$1_1") (pintype "bidirectional"))
      (node (ref "JP7") (pin "1") (pinfunction "P$1_1") (pintype "bidirectional"))
      (node (ref "PCB2") (pin "VIN") (pinfunction "VIN_VIN") (pintype "bidirectional"))
      (node (ref "R12") (pin "1") (pinfunction "1_1") (pintype "passive"))
      (node (ref "R15") (pin "1") (pinfunction "1_1") (pintype "passive"))
      (node (ref "R18") (pin "1") (pinfunction "1_1") (pintype "passive"))
      (node (ref "R21") (pin "1") (pinfunction "1_1") (pintype "passive"))
      (node (ref "R24") (pin "1") (pinfunction "1_1") (pintype "passive"))
      (node (ref "R27") (pin "1") (pinfunction "1_1") (pintype "passive"))
      (node (ref "R3") (pin "1") (pinfunction "1_1") (pintype "passive"))
      (node (ref "R30") (pin "1") (pinfunction "1_1") (pintype "passive"))
      (node (ref "U1") (pin "1") (pinfunction "INPUT_1") (pintype "input"))
    )
    (net (code "50") (name "unconnected-(PCB2-Pad3V3)") (class "Default")
      (node (ref "PCB2") (pin "3V3") (pinfunction "3V3_3V3") (pintype "bidirectional"))
    )
    (net (code "51") (name "unconnected-(PCB2-Pad5V)") (class "Default")
      (node (ref "PCB2") (pin "5V") (pinfunction "5V_5V") (pintype "bidirectional"))
    )
    (net (code "52") (name "unconnected-(PCB2-PadREF)") (class "Default")
      (node (ref "PCB2") (pin "REF") (pinfunction "REF_REF") (pintype "bidirectional"))
    )
    (net (code "53") (name "unconnected-(PCB2-PadRST)") (class "Default")
      (node (ref "PCB2") (pin "RST") (pinfunction "RST_RST") (pintype "bidirectional"))
    )
    (net (code "54") (name "unconnected-(PCB2-PadRST.)") (class "Default")
      (node (ref "PCB2") (pin "RST.") (pinfunction "RST._RST.") (pintype "bidirectional"))
    )
    (net (code "55") (name "unconnected-(PCB2-PadTX1)") (class "Default")
      (node (ref "PCB2") (pin "TX1") (pinfunction "TX1_TX1") (pintype "bidirectional"))
    )
    (net (code "56") (name "unconnected-(PCB2-RX0-PadRX1)") (class "Default")
      (node (ref "PCB2") (pin "RX1") (pinfunction "RX0_RX1") (pintype "bidirectional"))
    )
    (net (code "57") (name "unconnected-(U$1-CLKOUT{slash}SOF-Pad3)") (class "Default")
      (node (ref "U$1") (pin "3") (pinfunction "CLKOUT/SOF_3") (pintype "bidirectional"))
    )
    (net (code "58") (name "unconnected-(U$1-RX0BF{slash}-Pad11)") (class "Default")
      (node (ref "U$1") (pin "11") (pinfunction "RX0BF/_11") (pintype "bidirectional"))
    )
    (net (code "59") (name "unconnected-(U$1-RX1BF{slash}-Pad10)") (class "Default")
      (node (ref "U$1") (pin "10") (pinfunction "RX1BF/_10") (pintype "bidirectional"))
    )
    (net (code "60") (name "unconnected-(U$1-TX0RTS{slash}-Pad4)") (class "Default")
      (node (ref "U$1") (pin "4") (pinfunction "TX0RTS/_4") (pintype "bidirectional"))
    )
    (net (code "61") (name "unconnected-(U$1-TX1RTS{slash}-Pad5)") (class "Default")
      (node (ref "U$1") (pin "5") (pinfunction "TX1RTS/_5") (pintype "bidirectional"))
    )
    (net (code "62") (name "unconnected-(U$1-TX2RTS{slash}-Pad6)") (class "Default")
      (node (ref "U$1") (pin "6") (pinfunction "TX2RTS/_6") (pintype "bidirectional"))
    )
    (net (code "63") (name "unconnected-(U$2-VREF-Pad5)") (class "Default")
      (node (ref "U$2") (pin "5") (pinfunction "VREF_5") (pintype "output"))
    )
  )
)
